# FED3_v5_2_021419.net
KiCad netlist of a schematic drawn in EAGLE
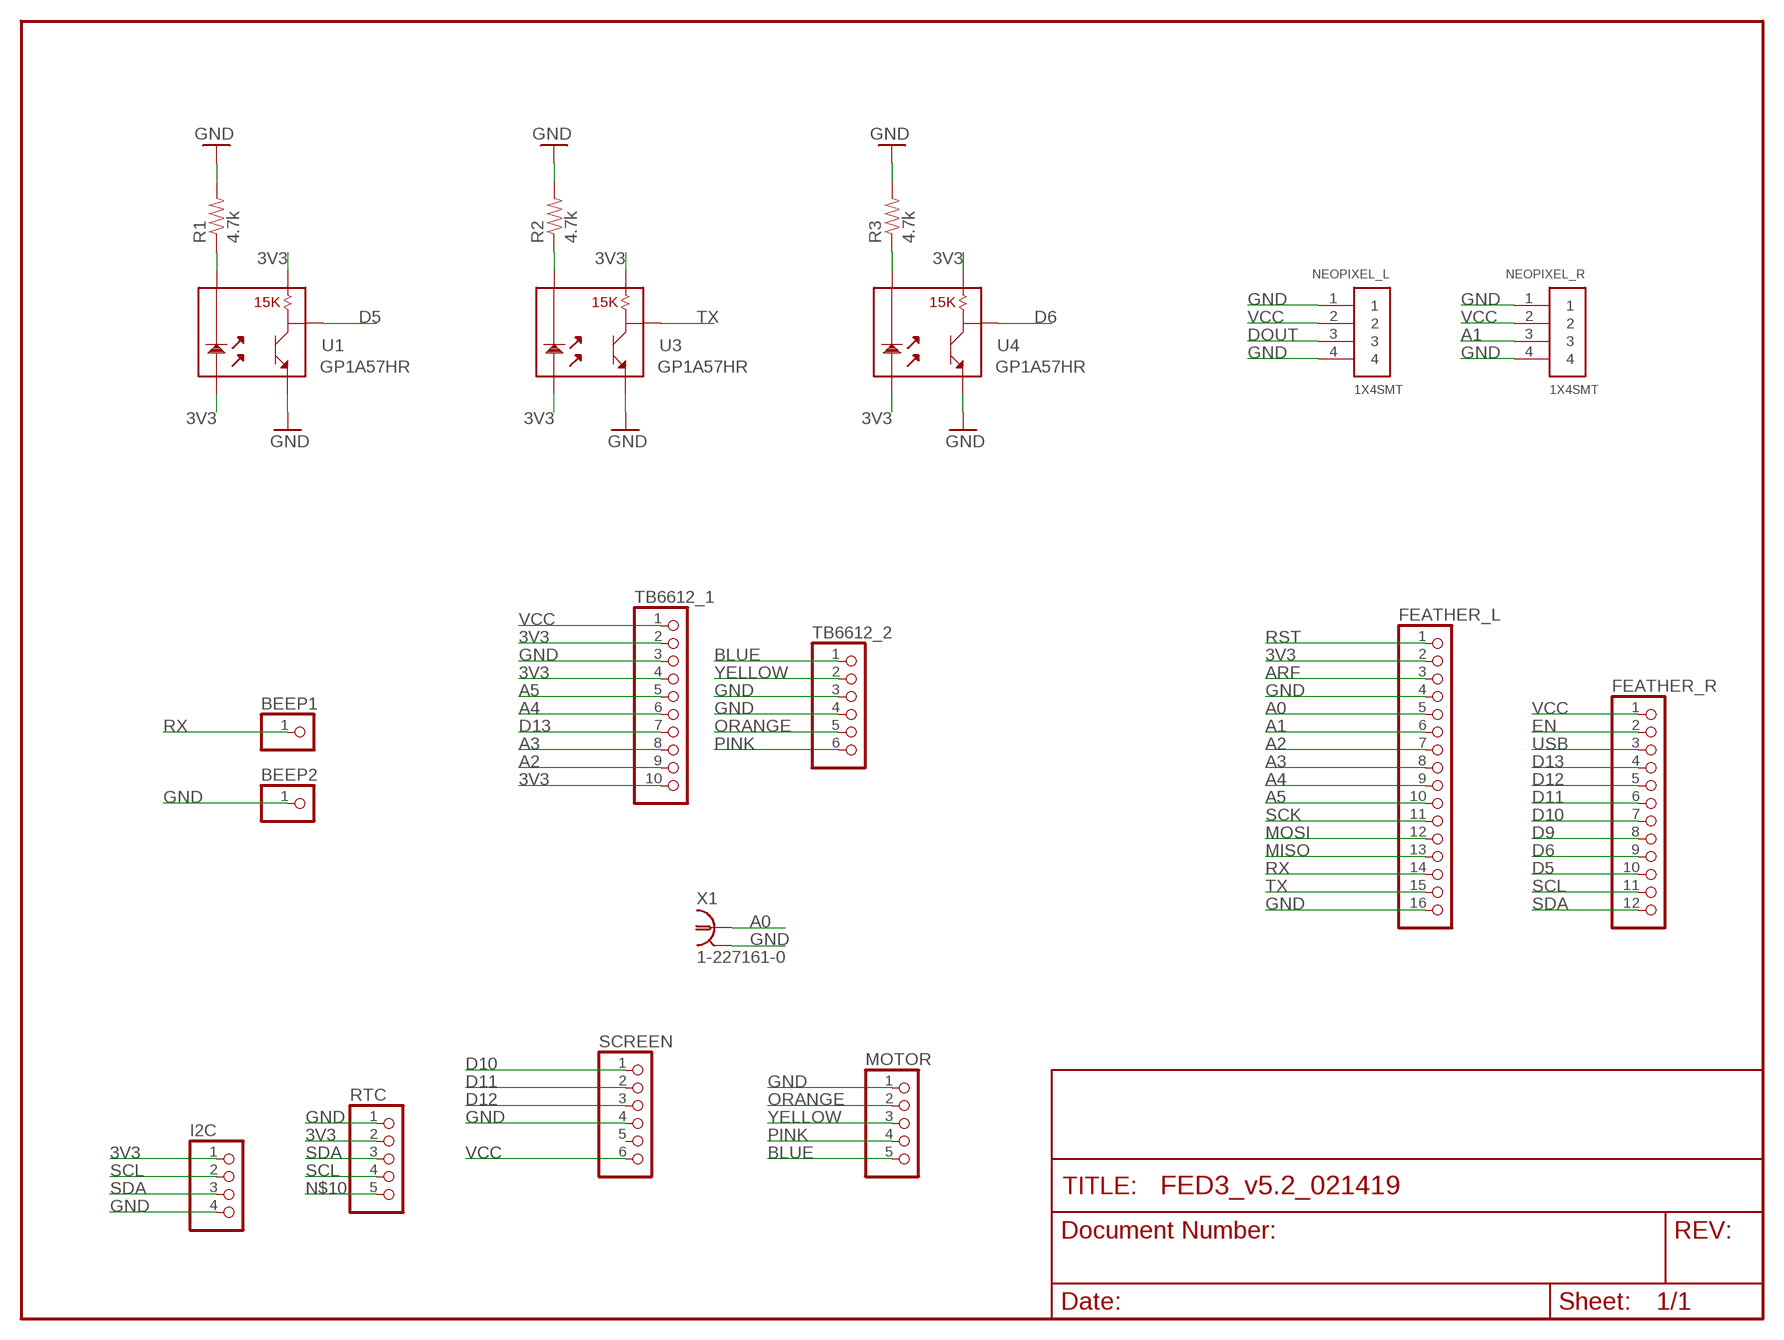
[diagram p0: schematic, sheet 1]

(export (version "E")
  (design (tool "Eeschema 10.0.6"))
  (components
    (comp (ref "BEEP1")
      (value "PINHD-1X1")
      (footprint "eagle-import:1X01")
      (libsource (lib "eagle-import") (part "PINHD-1X1"))
    )
    (comp (ref "BEEP2")
      (value "PINHD-1X1")
      (footprint "eagle-import:1X01")
      (libsource (lib "eagle-import") (part "PINHD-1X1"))
    )
    (comp (ref "FEATHER_L")
      (value "PINHD-1X16")
      (footprint "eagle-import:1X16")
      (libsource (lib "eagle-import") (part "PINHD-1X16"))
    )
    (comp (ref "FEATHER_R")
      (value "PINHD-1X12")
      (footprint "eagle-import:1X12")
      (libsource (lib "eagle-import") (part "PINHD-1X12"))
    )
    (comp (ref "I2C")
      (value "PINHD-1X4")
      (footprint "eagle-import:1X04")
      (libsource (lib "eagle-import") (part "PINHD-1X4"))
    )
    (comp (ref "MOTOR")
      (value "PINHD-1X5")
      (footprint "eagle-import:1X05")
      (libsource (lib "eagle-import") (part "PINHD-1X5"))
    )
    (comp (ref "NEOPIXEL_L")
      (value "1X4SMT")
      (footprint "eagle-import:1X4-SMT")
      (libsource (lib "eagle-import") (part "1X4SMT"))
    )
    (comp (ref "NEOPIXEL_R")
      (value "1X4SMT")
      (footprint "eagle-import:1X4-SMT")
      (libsource (lib "eagle-import") (part "1X4SMT"))
    )
    (comp (ref "R1")
      (value "4.7k")
      (footprint "eagle-import:AXIAL-0.3")
      (libsource (lib "eagle-import") (part "RESISTORPTH1"))
    )
    (comp (ref "R2")
      (value "4.7k")
      (footprint "eagle-import:AXIAL-0.3")
      (libsource (lib "eagle-import") (part "RESISTORPTH1"))
    )
    (comp (ref "R3")
      (value "4.7k")
      (footprint "eagle-import:AXIAL-0.3")
      (libsource (lib "eagle-import") (part "RESISTORPTH1"))
    )
    (comp (ref "RTC")
      (value "PINHD-1X5")
      (footprint "eagle-import:1X05")
      (libsource (lib "eagle-import") (part "PINHD-1X5"))
    )
    (comp (ref "SCREEN")
      (value "PINHD-1X6")
      (footprint "eagle-import:1X06")
      (libsource (lib "eagle-import") (part "PINHD-1X6"))
    )
    (comp (ref "TB6612_1")
      (value "PINHD-1X10")
      (footprint "eagle-import:1X10")
      (libsource (lib "eagle-import") (part "PINHD-1X10"))
    )
    (comp (ref "TB6612_2")
      (value "PINHD-1X6")
      (footprint "eagle-import:1X06")
      (libsource (lib "eagle-import") (part "PINHD-1X6"))
    )
    (comp (ref "U1")
      (value "GP1A57HR")
      (footprint "eagle-import:GP1A57HR")
      (libsource (lib "eagle-import") (part "GP1A57HR"))
    )
    (comp (ref "U3")
      (value "GP1A57HR")
      (footprint "eagle-import:GP1A57HR")
      (libsource (lib "eagle-import") (part "GP1A57HR"))
    )
    (comp (ref "U4")
      (value "GP1A57HR")
      (footprint "eagle-import:GP1A57HR")
      (libsource (lib "eagle-import") (part "GP1A57HR"))
    )
    (comp (ref "X1")
      (value "1-227161-0")
      (footprint "eagle-import:AMP_227161")
      (fields (field (name "MF") "TYCO ELECTRONICS") (field (name "MPN") "1-227161"))
      (libsource (lib "eagle-import") (part "?2271611--0"))
    )
  )
  (nets
    (net (code "1") (name "/3V3") (class "Default")
      (node (ref "FEATHER_L") (pin "2") (pinfunction "2_2") (pintype "passive"))
      (node (ref "I2C") (pin "1") (pinfunction "1_1") (pintype "passive"))
      (node (ref "RTC") (pin "2") (pinfunction "2_2") (pintype "passive"))
      (node (ref "TB6612_1") (pin "10") (pinfunction "10_10") (pintype "passive"))
      (node (ref "TB6612_1") (pin "2") (pinfunction "2_2") (pintype "passive"))
      (node (ref "TB6612_1") (pin "4") (pinfunction "4_4") (pintype "passive"))
      (node (ref "U1") (pin "1") (pinfunction "1_1") (pintype "bidirectional"))
      (node (ref "U1") (pin "3") (pinfunction "3_3") (pintype "bidirectional"))
      (node (ref "U3") (pin "1") (pinfunction "1_1") (pintype "bidirectional"))
      (node (ref "U3") (pin "3") (pinfunction "3_3") (pintype "bidirectional"))
      (node (ref "U4") (pin "1") (pinfunction "1_1") (pintype "bidirectional"))
      (node (ref "U4") (pin "3") (pinfunction "3_3") (pintype "bidirectional"))
    )
    (net (code "2") (name "/A0") (class "Default")
      (node (ref "FEATHER_L") (pin "5") (pinfunction "5_5") (pintype "passive"))
      (node (ref "X1") (pin "1") (pinfunction "1_1") (pintype "passive"))
    )
    (net (code "3") (name "/A1") (class "Default")
      (node (ref "FEATHER_L") (pin "6") (pinfunction "6_6") (pintype "passive"))
      (node (ref "NEOPIXEL_R") (pin "3") (pinfunction "3_3") (pintype "bidirectional"))
    )
    (net (code "4") (name "/A2") (class "Default")
      (node (ref "FEATHER_L") (pin "7") (pinfunction "7_7") (pintype "passive"))
      (node (ref "TB6612_1") (pin "9") (pinfunction "9_9") (pintype "passive"))
    )
    (net (code "5") (name "/A3") (class "Default")
      (node (ref "FEATHER_L") (pin "8") (pinfunction "8_8") (pintype "passive"))
      (node (ref "TB6612_1") (pin "8") (pinfunction "8_8") (pintype "passive"))
    )
    (net (code "6") (name "/A4") (class "Default")
      (node (ref "FEATHER_L") (pin "9") (pinfunction "9_9") (pintype "passive"))
      (node (ref "TB6612_1") (pin "6") (pinfunction "6_6") (pintype "passive"))
    )
    (net (code "7") (name "/A5") (class "Default")
      (node (ref "FEATHER_L") (pin "10") (pinfunction "10_10") (pintype "passive"))
      (node (ref "TB6612_1") (pin "5") (pinfunction "5_5") (pintype "passive"))
    )
    (net (code "8") (name "/ARF") (class "Default")
      (node (ref "FEATHER_L") (pin "3") (pinfunction "3_3") (pintype "passive"))
    )
    (net (code "9") (name "/BLUE") (class "Default")
      (node (ref "MOTOR") (pin "5") (pinfunction "5_5") (pintype "passive"))
      (node (ref "TB6612_2") (pin "1") (pinfunction "1_1") (pintype "passive"))
    )
    (net (code "10") (name "/D5") (class "Default")
      (node (ref "FEATHER_R") (pin "10") (pinfunction "10_10") (pintype "passive"))
      (node (ref "U1") (pin "4") (pinfunction "4_4") (pintype "bidirectional"))
    )
    (net (code "11") (name "/D6") (class "Default")
      (node (ref "FEATHER_R") (pin "9") (pinfunction "9_9") (pintype "passive"))
      (node (ref "U4") (pin "4") (pinfunction "4_4") (pintype "bidirectional"))
    )
    (net (code "12") (name "/D9") (class "Default")
      (node (ref "FEATHER_R") (pin "8") (pinfunction "8_8") (pintype "passive"))
    )
    (net (code "13") (name "/D10") (class "Default")
      (node (ref "FEATHER_R") (pin "7") (pinfunction "7_7") (pintype "passive"))
      (node (ref "SCREEN") (pin "1") (pinfunction "1_1") (pintype "passive"))
    )
    (net (code "14") (name "/D11") (class "Default")
      (node (ref "FEATHER_R") (pin "6") (pinfunction "6_6") (pintype "passive"))
      (node (ref "SCREEN") (pin "2") (pinfunction "2_2") (pintype "passive"))
    )
    (net (code "15") (name "/D12") (class "Default")
      (node (ref "FEATHER_R") (pin "5") (pinfunction "5_5") (pintype "passive"))
      (node (ref "SCREEN") (pin "3") (pinfunction "3_3") (pintype "passive"))
    )
    (net (code "16") (name "/D13") (class "Default")
      (node (ref "FEATHER_R") (pin "4") (pinfunction "4_4") (pintype "passive"))
      (node (ref "TB6612_1") (pin "7") (pinfunction "7_7") (pintype "passive"))
    )
    (net (code "17") (name "/DOUT") (class "Default")
      (node (ref "NEOPIXEL_L") (pin "3") (pinfunction "3_3") (pintype "bidirectional"))
    )
    (net (code "18") (name "/EN") (class "Default")
      (node (ref "FEATHER_R") (pin "2") (pinfunction "2_2") (pintype "passive"))
    )
    (net (code "19") (name "/MISO") (class "Default")
      (node (ref "FEATHER_L") (pin "13") (pinfunction "13_13") (pintype "passive"))
    )
    (net (code "20") (name "/MOSI") (class "Default")
      (node (ref "FEATHER_L") (pin "12") (pinfunction "12_12") (pintype "passive"))
    )
    (net (code "21") (name "/N$10") (class "Default")
      (node (ref "RTC") (pin "5") (pinfunction "5_5") (pintype "passive"))
    )
    (net (code "22") (name "/ORANGE") (class "Default")
      (node (ref "MOTOR") (pin "2") (pinfunction "2_2") (pintype "passive"))
      (node (ref "TB6612_2") (pin "5") (pinfunction "5_5") (pintype "passive"))
    )
    (net (code "23") (name "/PINK") (class "Default")
      (node (ref "MOTOR") (pin "4") (pinfunction "4_4") (pintype "passive"))
      (node (ref "TB6612_2") (pin "6") (pinfunction "6_6") (pintype "passive"))
    )
    (net (code "24") (name "/RST") (class "Default")
      (node (ref "FEATHER_L") (pin "1") (pinfunction "1_1") (pintype "passive"))
    )
    (net (code "25") (name "/RX") (class "Default")
      (node (ref "BEEP1") (pin "1") (pinfunction "1_1") (pintype "passive"))
      (node (ref "FEATHER_L") (pin "14") (pinfunction "14_14") (pintype "passive"))
    )
    (net (code "26") (name "/SCK") (class "Default")
      (node (ref "FEATHER_L") (pin "11") (pinfunction "11_11") (pintype "passive"))
    )
    (net (code "27") (name "/SCL") (class "Default")
      (node (ref "FEATHER_R") (pin "11") (pinfunction "11_11") (pintype "passive"))
      (node (ref "I2C") (pin "2") (pinfunction "2_2") (pintype "passive"))
      (node (ref "RTC") (pin "4") (pinfunction "4_4") (pintype "passive"))
    )
    (net (code "28") (name "/SDA") (class "Default")
      (node (ref "FEATHER_R") (pin "12") (pinfunction "12_12") (pintype "passive"))
      (node (ref "I2C") (pin "3") (pinfunction "3_3") (pintype "passive"))
      (node (ref "RTC") (pin "3") (pinfunction "3_3") (pintype "passive"))
    )
    (net (code "29") (name "/TX") (class "Default")
      (node (ref "FEATHER_L") (pin "15") (pinfunction "15_15") (pintype "passive"))
      (node (ref "U3") (pin "4") (pinfunction "4_4") (pintype "bidirectional"))
    )
    (net (code "30") (name "/USB") (class "Default")
      (node (ref "FEATHER_R") (pin "3") (pinfunction "3_3") (pintype "passive"))
    )
    (net (code "31") (name "/VCC") (class "Default")
      (node (ref "FEATHER_R") (pin "1") (pinfunction "1_1") (pintype "passive"))
      (node (ref "NEOPIXEL_L") (pin "2") (pinfunction "2_2") (pintype "bidirectional"))
      (node (ref "NEOPIXEL_R") (pin "2") (pinfunction "2_2") (pintype "bidirectional"))
      (node (ref "SCREEN") (pin "6") (pinfunction "6_6") (pintype "passive"))
      (node (ref "TB6612_1") (pin "1") (pinfunction "1_1") (pintype "passive"))
    )
    (net (code "32") (name "/YELLOW") (class "Default")
      (node (ref "MOTOR") (pin "3") (pinfunction "3_3") (pintype "passive"))
      (node (ref "TB6612_2") (pin "2") (pinfunction "2_2") (pintype "passive"))
    )
    (net (code "33") (name "GND") (class "Default")
      (node (ref "BEEP2") (pin "1") (pinfunction "1_1") (pintype "passive"))
      (node (ref "FEATHER_L") (pin "16") (pinfunction "16_16") (pintype "passive"))
      (node (ref "FEATHER_L") (pin "4") (pinfunction "4_4") (pintype "passive"))
      (node (ref "I2C") (pin "4") (pinfunction "4_4") (pintype "passive"))
      (node (ref "MOTOR") (pin "1") (pinfunction "1_1") (pintype "passive"))
      (node (ref "NEOPIXEL_L") (pin "1") (pinfunction "1_1") (pintype "bidirectional"))
      (node (ref "NEOPIXEL_L") (pin "4") (pinfunction "4_4") (pintype "bidirectional"))
      (node (ref "NEOPIXEL_R") (pin "1") (pinfunction "1_1") (pintype "bidirectional"))
      (node (ref "NEOPIXEL_R") (pin "4") (pinfunction "4_4") (pintype "bidirectional"))
      (node (ref "R1") (pin "P$2") (pinfunction "2_P$2") (pintype "passive"))
      (node (ref "R2") (pin "P$2") (pinfunction "2_P$2") (pintype "passive"))
      (node (ref "R3") (pin "P$2") (pinfunction "2_P$2") (pintype "passive"))
      (node (ref "RTC") (pin "1") (pinfunction "1_1") (pintype "passive"))
      (node (ref "SCREEN") (pin "4") (pinfunction "4_4") (pintype "passive"))
      (node (ref "TB6612_1") (pin "3") (pinfunction "3_3") (pintype "passive"))
      (node (ref "TB6612_2") (pin "3") (pinfunction "3_3") (pintype "passive"))
      (node (ref "TB6612_2") (pin "4") (pinfunction "4_4") (pintype "passive"))
      (node (ref "U1") (pin "5") (pinfunction "5_5") (pintype "bidirectional"))
      (node (ref "U3") (pin "5") (pinfunction "5_5") (pintype "bidirectional"))
      (node (ref "U4") (pin "5") (pinfunction "5_5") (pintype "bidirectional"))
      (node (ref "X1") (pin "2") (pinfunction "2_2") (pintype "passive"))
    )
    (net (code "34") (name "Net-(R1-1)") (class "Default")
      (node (ref "R1") (pin "P$1") (pinfunction "1_P$1") (pintype "passive"))
      (node (ref "U1") (pin "2") (pinfunction "2_2") (pintype "bidirectional"))
    )
    (net (code "35") (name "Net-(R2-1)") (class "Default")
      (node (ref "R2") (pin "P$1") (pinfunction "1_P$1") (pintype "passive"))
      (node (ref "U3") (pin "2") (pinfunction "2_2") (pintype "bidirectional"))
    )
    (net (code "36") (name "Net-(R3-1)") (class "Default")
      (node (ref "R3") (pin "P$1") (pinfunction "1_P$1") (pintype "passive"))
      (node (ref "U4") (pin "2") (pinfunction "2_2") (pintype "bidirectional"))
    )
    (net (code "37") (name "unconnected-(SCREEN-Pad5)") (class "Default")
      (node (ref "SCREEN") (pin "5") (pinfunction "5_5") (pintype "passive"))
    )
  )
)
